# LB-w17-XOR-v03_1_2.net
KiCad netlist of a schematic drawn in EAGLE
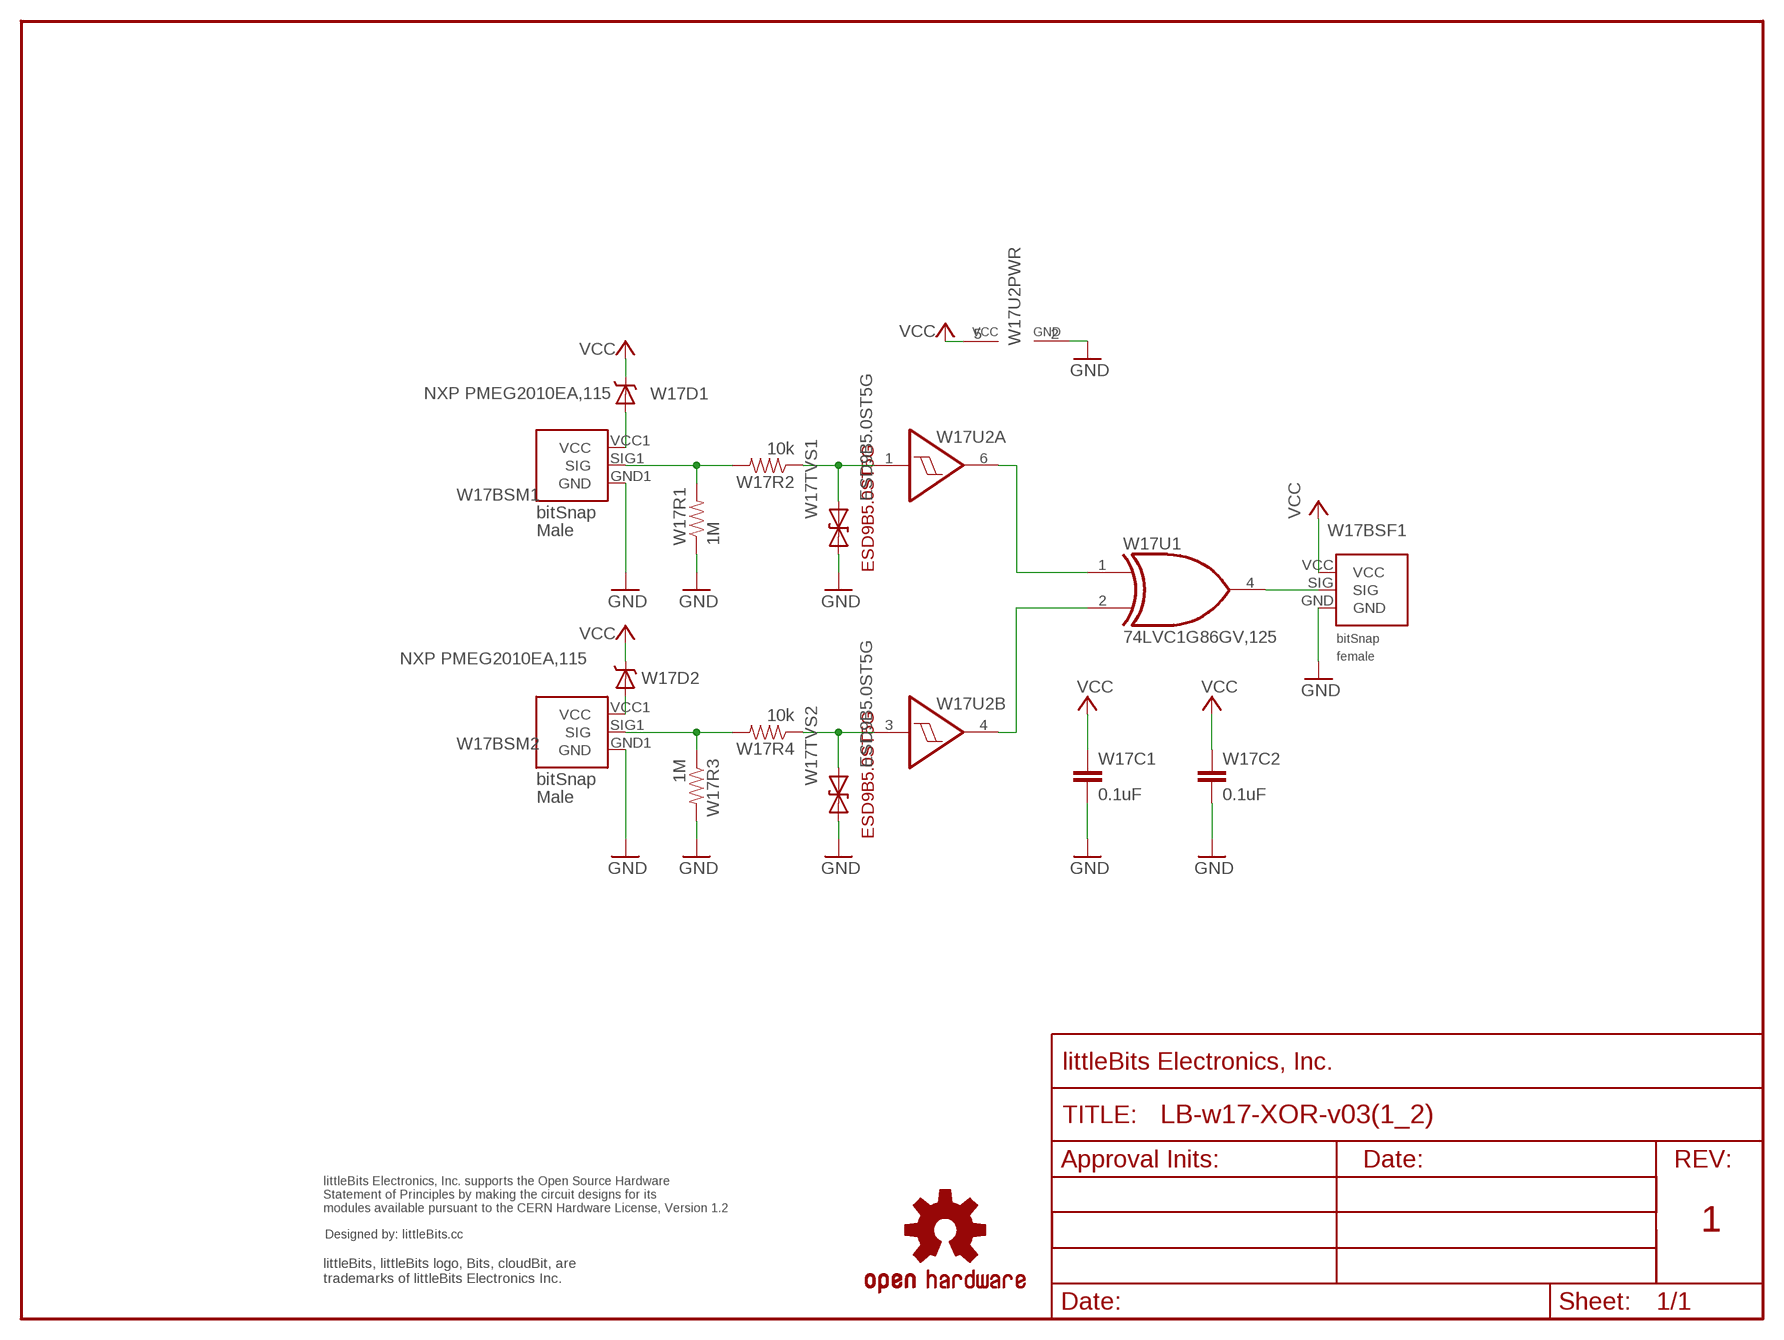
[diagram p0: schematic, sheet 1]

(export (version "E")
  (design (tool "Eeschema 10.0.6"))
  (components
    (comp (ref "U$1")
      (value "FRAME-LETTER-OHWOHW")
      (footprint "eagle-import:FABDWG01-OHW")
      (libsource (lib "eagle-import") (part "FRAME-LETTER-OHWOHW"))
    )
    (comp (ref "U$2")
      (value "OSHW-LOGOL")
      (footprint "eagle-import:OSHW-LOGO-L")
      (libsource (lib "eagle-import") (part "OSHW-LOGOL"))
    )
    (comp (ref "U$5")
      (value "OSHWCREDIT")
      (footprint "eagle-import:OSHWCREDIT")
      (libsource (lib "eagle-import") (part "OSHWCREDIT"))
    )
    (comp (ref "W17BSF1")
      (value "BITSNAP_V03_FEMALE")
      (footprint "eagle-import:BITSNAP_V03_FEMALE")
      (libsource (lib "eagle-import") (part "BITSNAP_V03_FEMALE"))
    )
    (comp (ref "W17BSM1")
      (value "BITSNAP_V03_MALE")
      (footprint "eagle-import:BITSNAP_V03_MALE")
      (libsource (lib "eagle-import") (part "BITSNAP_V03_MALE"))
    )
    (comp (ref "W17BSM2")
      (value "BITSNAP_V03_MALE")
      (footprint "eagle-import:BITSNAP_V03_MALE")
      (libsource (lib "eagle-import") (part "BITSNAP_V03_MALE"))
    )
    (comp (ref "W17C1")
      (value "0.1uF")
      (footprint "eagle-import:CAP-0603")
      (libsource (lib "eagle-import") (part "CAPCAP-0603"))
    )
    (comp (ref "W17C2")
      (value "0.1uF")
      (footprint "eagle-import:CAP-0603")
      (libsource (lib "eagle-import") (part "CAPCAP-0603"))
    )
    (comp (ref "W17D1")
      (value "NXP PMEG2010EA,115")
      (footprint "eagle-import:SOD-323")
      (libsource (lib "eagle-import") (part "DIODE-SCHOTTKY"))
    )
    (comp (ref "W17D2")
      (value "NXP PMEG2010EA,115")
      (footprint "eagle-import:SOD-323")
      (libsource (lib "eagle-import") (part "DIODE-SCHOTTKY"))
    )
    (comp (ref "W17R1")
      (value "1M")
      (footprint "eagle-import:0603-RES")
      (libsource (lib "eagle-import") (part "RESISTOR0603-RES"))
    )
    (comp (ref "W17R2")
      (value "10k")
      (footprint "eagle-import:0603-RES")
      (libsource (lib "eagle-import") (part "RESISTOR0603-RES"))
    )
    (comp (ref "W17R3")
      (value "1M")
      (footprint "eagle-import:0603-RES")
      (libsource (lib "eagle-import") (part "RESISTOR0603-RES"))
    )
    (comp (ref "W17R4")
      (value "10k")
      (footprint "eagle-import:0603-RES")
      (libsource (lib "eagle-import") (part "RESISTOR0603-RES"))
    )
    (comp (ref "W17TVS1")
      (value "ESD9B5.0ST5G")
      (footprint "eagle-import:SOD-923")
      (libsource (lib "eagle-import") (part "DIODE-TVSSOD-923"))
    )
    (comp (ref "W17TVS2")
      (value "ESD9B5.0ST5G")
      (footprint "eagle-import:SOD-923")
      (libsource (lib "eagle-import") (part "DIODE-TVSSOD-923"))
    )
    (comp (ref "W17U1")
      (value "74LVC1G86GV,125")
      (footprint "eagle-import:SOT23-5")
      (libsource (lib "eagle-import") (part "741G86DBVAHC"))
    )
    (comp (ref "W17U2")
      (value "NC7WZ17P6X")
      (footprint "eagle-import:SC70-6")
      (libsource (lib "eagle-import") (part "SCHMITT_TRIGGER_NON_INVERTINGNC7WZ17"))
    )
  )
  (nets
    (net (code "1") (name "GND") (class "Default")
      (node (ref "W17BSF1") (pin "GND") (pinfunction "GND_GND") (pintype "bidirectional"))
      (node (ref "W17BSM1") (pin "GND1") (pinfunction "GND_GND1") (pintype "bidirectional"))
      (node (ref "W17BSM2") (pin "GND1") (pinfunction "GND_GND1") (pintype "bidirectional"))
      (node (ref "W17C1") (pin "2") (pinfunction "2_2") (pintype "passive"))
      (node (ref "W17C2") (pin "2") (pinfunction "2_2") (pintype "passive"))
      (node (ref "W17R1") (pin "1") (pinfunction "1_1") (pintype "passive"))
      (node (ref "W17R3") (pin "2") (pinfunction "2_2") (pintype "passive"))
      (node (ref "W17TVS1") (pin "1") (pinfunction "A_1") (pintype "passive"))
      (node (ref "W17TVS2") (pin "1") (pinfunction "A_1") (pintype "passive"))
      (node (ref "W17U2") (pin "2") (pinfunction "GND_2") (pintype "power_in"))
    )
    (net (code "2") (name "Net-(W17BSM1-SIG)") (class "Default")
      (node (ref "W17BSM1") (pin "SIG1") (pinfunction "SIG_SIG1") (pintype "bidirectional"))
      (node (ref "W17R1") (pin "2") (pinfunction "2_2") (pintype "passive"))
      (node (ref "W17R2") (pin "2") (pinfunction "2_2") (pintype "passive"))
    )
    (net (code "3") (name "Net-(W17BSM1-VCC)") (class "Default")
      (node (ref "W17BSM1") (pin "VCC1") (pinfunction "VCC_VCC1") (pintype "bidirectional"))
      (node (ref "W17D1") (pin "2") (pinfunction "A_2") (pintype "passive"))
    )
    (net (code "4") (name "Net-(W17BSM2-SIG)") (class "Default")
      (node (ref "W17BSM2") (pin "SIG1") (pinfunction "SIG_SIG1") (pintype "bidirectional"))
      (node (ref "W17R3") (pin "1") (pinfunction "1_1") (pintype "passive"))
      (node (ref "W17R4") (pin "2") (pinfunction "2_2") (pintype "passive"))
    )
    (net (code "5") (name "Net-(W17BSM2-VCC)") (class "Default")
      (node (ref "W17BSM2") (pin "VCC1") (pinfunction "VCC_VCC1") (pintype "bidirectional"))
      (node (ref "W17D2") (pin "2") (pinfunction "A_2") (pintype "passive"))
    )
    (net (code "6") (name "Net-(W17TVS1-C)") (class "Default")
      (node (ref "W17R2") (pin "1") (pinfunction "1_1") (pintype "passive"))
      (node (ref "W17TVS1") (pin "2") (pinfunction "C_2") (pintype "passive"))
      (node (ref "W17U2") (pin "1") (pinfunction "I_1") (pintype "input"))
    )
    (net (code "7") (name "Net-(W17TVS2-C)") (class "Default")
      (node (ref "W17R4") (pin "1") (pinfunction "1_1") (pintype "passive"))
      (node (ref "W17TVS2") (pin "2") (pinfunction "C_2") (pintype "passive"))
      (node (ref "W17U2") (pin "3") (pinfunction "I_3") (pintype "input"))
    )
    (net (code "8") (name "Net-(W17U1A-I0)") (class "Default")
      (node (ref "W17U1") (pin "1") (pinfunction "I0_1") (pintype "input"))
      (node (ref "W17U2") (pin "6") (pinfunction "O_6") (pintype "output"))
    )
    (net (code "9") (name "Net-(W17U1A-I1)") (class "Default")
      (node (ref "W17U1") (pin "2") (pinfunction "I1_2") (pintype "input"))
      (node (ref "W17U2") (pin "4") (pinfunction "O_4") (pintype "output"))
    )
    (net (code "10") (name "Net-(W17U1A-O)") (class "Default")
      (node (ref "W17BSF1") (pin "SIG") (pinfunction "SIG_SIG") (pintype "bidirectional"))
      (node (ref "W17U1") (pin "4") (pinfunction "O_4") (pintype "output"))
    )
    (net (code "11") (name "VCC") (class "Default")
      (node (ref "W17BSF1") (pin "VCC") (pinfunction "VCC_VCC") (pintype "bidirectional"))
      (node (ref "W17C1") (pin "1") (pinfunction "1_1") (pintype "passive"))
      (node (ref "W17C2") (pin "1") (pinfunction "1_1") (pintype "passive"))
      (node (ref "W17D1") (pin "1") (pinfunction "C_1") (pintype "passive"))
      (node (ref "W17D2") (pin "1") (pinfunction "C_1") (pintype "passive"))
      (node (ref "W17U2") (pin "5") (pinfunction "VCC_5") (pintype "power_in"))
    )
  )
)
